# DAC_ADC_MAX5841_MAX1037.net
KiCad netlist of a schematic drawn in Altium Designer
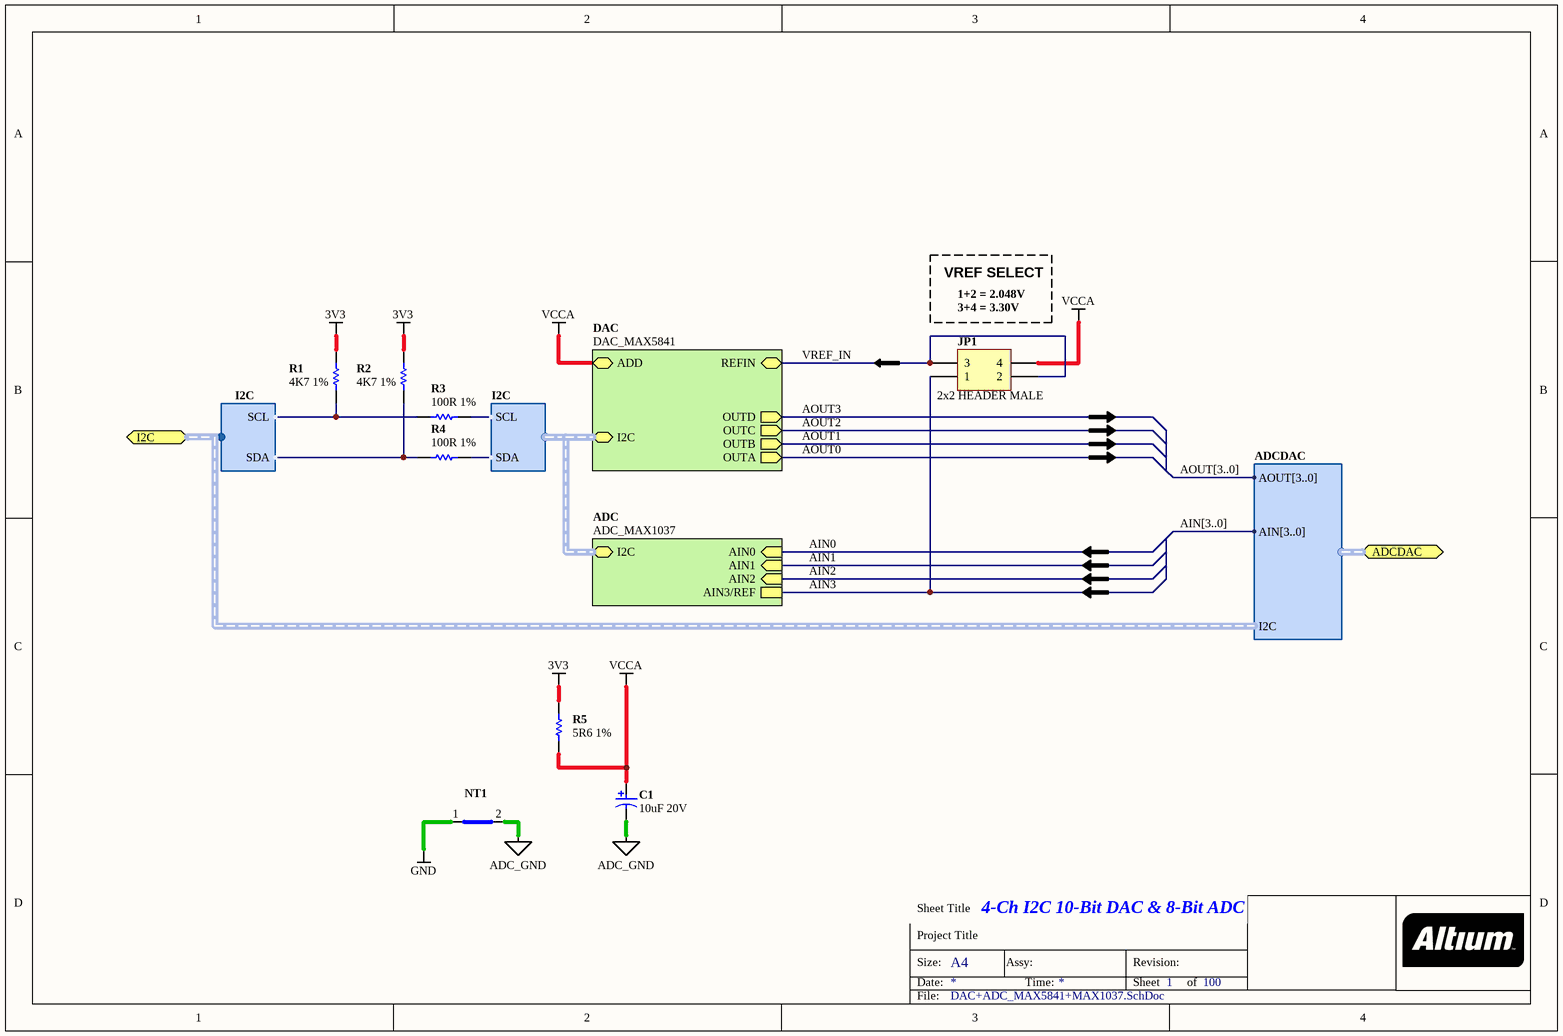
[diagram p0: DAC+ADC_MAX5841+MAX1037.SchDoc]

(export (version "E")
  (design (tool "Eeschema 10.0.6"))
  (components
    (comp (ref "C1")
      (value "10uF 20V")
      (footprint "CAPC3528-STAR")
      (description "Capacitor, Tantalum, 10uF 10% 20V MCCT-B (3528)")
      (fields (field (name "TOLERANCE") "10 %"))
      (libsource (lib "altium-import") (part "root_0_CAP-P_"))
    )
    (comp (ref "JP1")
      (value "2x2 HEADER MALE")
      (footprint "HDR2X2")
      (description "Header IDC, 2 x 2 Pin Vertical 2.54mm Pitch (Non-Boxed, Male)")
      (libsource (lib "AltiumDesignLibrary") (part "CON-HDR-2x2-STR"))
    )
    (comp (ref "NT1")
      (value "Net Tie SMT2")
      (footprint "NETTIE-SMT2-16X11")
      (description "Net-Tie, Surface Mount, 2 x 0.8mm x 0.4mm SMT Pads - For 0.4mm Track")
      (libsource (lib "AltiumDesignLibrary") (part "NETTIE-SMT2"))
    )
    (comp (ref "R1")
      (value "4K7 1%")
      (footprint "RESC1005-STAR")
      (description "Resistor, 4K7 1% 0402 (1005)")
      (fields (field (name "TOLERANCE") "1 %"))
      (libsource (lib "altium-import") (part "root_0_RES_"))
    )
    (comp (ref "R2")
      (value "4K7 1%")
      (footprint "RESC1005-STAR")
      (description "Resistor, 4K7 1% 0402 (1005)")
      (fields (field (name "TOLERANCE") "1 %"))
      (libsource (lib "altium-import") (part "root_0_RES_"))
    )
    (comp (ref "R3")
      (value "100R 1%")
      (footprint "RESC1005-STAR")
      (description "Resistor, 100R 1% 0402 (1005)")
      (fields (field (name "TOLERANCE") "1 %"))
      (libsource (lib "altium-import") (part "root_1_RES_"))
    )
    (comp (ref "R4")
      (value "100R 1%")
      (footprint "RESC1005-STAR")
      (description "Resistor, 100R 1% 0402 (1005)")
      (fields (field (name "TOLERANCE") "1 %"))
      (libsource (lib "altium-import") (part "root_1_RES_"))
    )
    (comp (ref "R5")
      (value "5R6 1%")
      (footprint "RESC1005-STAR")
      (description "Resistor, 5R6 1% 0402 (1005)")
      (fields (field (name "TOLERANCE") "1 %"))
      (libsource (lib "AltiumDesignLibrary") (part "RES"))
    )
  )
  (nets
    (net (code "8") (name "/AIN3") (class "Default")
      (node (ref "JP1") (pin "1") (pinfunction "1_1") (pintype "passive"))
    )
    (net (code "15") (name "/VREF_IN") (class "Default")
      (node (ref "JP1") (pin "2") (pinfunction "2_2") (pintype "passive"))
      (node (ref "JP1") (pin "3") (pinfunction "3_3") (pintype "passive"))
    )
    (net (code "18") (name "3V3") (class "Default")
      (node (ref "R1") (pin "1") (pinfunction "1_1") (pintype "passive"))
      (node (ref "R2") (pin "1") (pinfunction "1_1") (pintype "passive"))
      (node (ref "R5") (pin "2") (pinfunction "2_2") (pintype "passive"))
    )
    (net (code "19") (name "ADC_GND") (class "Default")
      (node (ref "C1") (pin "2") (pinfunction "2_2") (pintype "passive"))
      (node (ref "NT1") (pin "2") (pinfunction "Net2_2") (pintype "passive"))
    )
    (net (code "20") (name "GND") (class "Default")
      (node (ref "NT1") (pin "1") (pinfunction "Net1_1") (pintype "passive"))
    )
    (net (code "21") (name "Net-(R1-Pad2)") (class "Default")
      (node (ref "R1") (pin "2") (pinfunction "2_2") (pintype "passive"))
      (node (ref "R3") (pin "1") (pinfunction "1_1") (pintype "passive"))
    )
    (net (code "22") (name "Net-(R2-Pad2)") (class "Default")
      (node (ref "R2") (pin "2") (pinfunction "2_2") (pintype "passive"))
      (node (ref "R4") (pin "1") (pinfunction "1_1") (pintype "passive"))
    )
    (net (code "23") (name "VCCA") (class "Default")
      (node (ref "C1") (pin "1") (pinfunction "1_1") (pintype "passive"))
      (node (ref "JP1") (pin "4") (pinfunction "4_4") (pintype "passive"))
      (node (ref "R5") (pin "1") (pinfunction "1_1") (pintype "passive"))
    )
    (net (code "24") (name "unconnected-(R3-Pad2)") (class "Default")
      (node (ref "R3") (pin "2") (pinfunction "2_2") (pintype "passive"))
    )
    (net (code "25") (name "unconnected-(R4-Pad2)") (class "Default")
      (node (ref "R4") (pin "2") (pinfunction "2_2") (pintype "passive"))
    )
  )
)
